# PinguinoUCAB.net
KiCad netlist of a schematic drawn in EAGLE
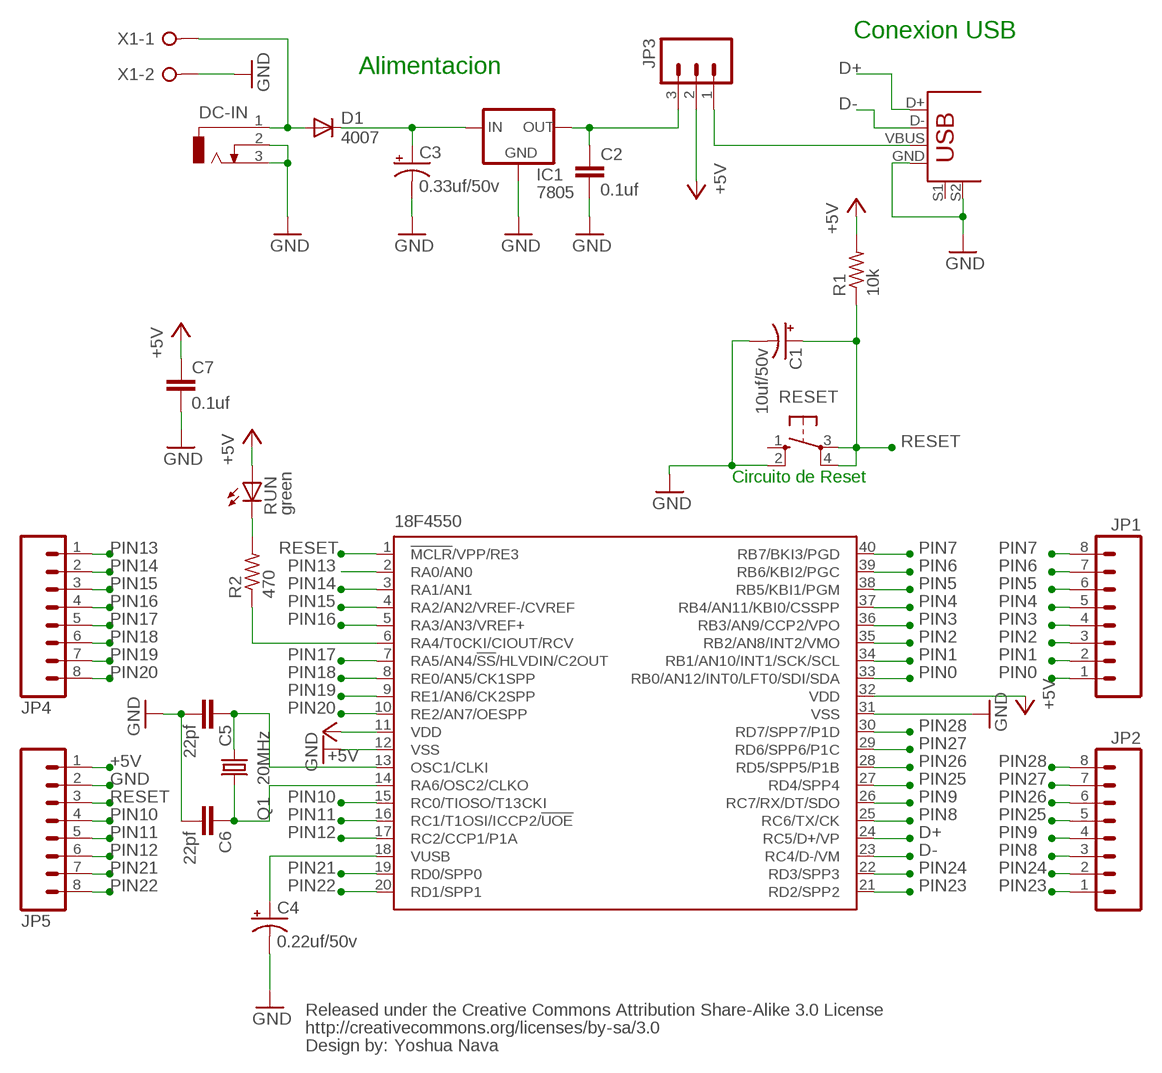
[diagram p0: schematic, sheet 1]

(export (version "E")
  (design (tool "Eeschema 10.0.6"))
  (components
    (comp (ref "18F4550")
      (value "PIC18F4550_40")
      (footprint "eagle-import:DIL40")
      (fields (field (name "MF") "MICROCHIP") (field (name "MPN") "PIC18F4550-I/P"))
      (libsource (lib "eagle-import") (part "PIC18F4_40550"))
    )
    (comp (ref "C1")
      (value "10uf/50v")
      (footprint "eagle-import:CPOL-RADIAL-10UF-25V")
      (libsource (lib "eagle-import") (part "CAP_POLPTH2"))
    )
    (comp (ref "C2")
      (value "0.1uf")
      (footprint "eagle-import:CAP-PTH-SMALL2")
      (libsource (lib "eagle-import") (part "CAPPTH2"))
    )
    (comp (ref "C3")
      (value "0.33uf/50v")
      (footprint "eagle-import:CPOL-RADIAL-10UF-25V")
      (libsource (lib "eagle-import") (part "CAP_POLPTH2"))
    )
    (comp (ref "C4")
      (value "0.22uf/50v")
      (footprint "eagle-import:CPOL-RADIAL-10UF-25V")
      (libsource (lib "eagle-import") (part "CAP_POLPTH2"))
    )
    (comp (ref "C5")
      (value "22pf")
      (footprint "eagle-import:CAP-PTH-SMALL2")
      (libsource (lib "eagle-import") (part "CAPPTH2"))
    )
    (comp (ref "C6")
      (value "22pf")
      (footprint "eagle-import:CAP-PTH-SMALL2")
      (libsource (lib "eagle-import") (part "CAPPTH2"))
    )
    (comp (ref "C7")
      (value "0.1uf")
      (footprint "eagle-import:CAP-PTH-SMALL2")
      (libsource (lib "eagle-import") (part "CAPPTH2"))
    )
    (comp (ref "CC_TEXT1")
      (value "CREATIVE_COMMONS")
      (footprint "eagle-import:CREATIVE_COMMONS")
      (libsource (lib "eagle-import") (part "CREATIVE_COMMONS"))
    )
    (comp (ref "D1")
      (value "4007")
      (footprint "eagle-import:DO35-7")
      (libsource (lib "eagle-import") (part "1N4148DO35-7"))
    )
    (comp (ref "DC-IN")
      (value "DCJ0303")
      (footprint "eagle-import:DCJ0303")
      (libsource (lib "eagle-import") (part "DCJ0303"))
    )
    (comp (ref "IC1")
      (value "7805")
      (footprint "eagle-import:78XXL")
      (libsource (lib "eagle-import") (part "78XXL"))
    )
    (comp (ref "JP1")
      (value "M08LONGPADS")
      (footprint "eagle-import:1X08_LONGPADS")
      (libsource (lib "eagle-import") (part "M08LONGPADS"))
    )
    (comp (ref "JP2")
      (value "M08LONGPADS")
      (footprint "eagle-import:1X08_LONGPADS")
      (libsource (lib "eagle-import") (part "M08LONGPADS"))
    )
    (comp (ref "JP3")
      (value "M03LONGPADS")
      (footprint "eagle-import:1X03_LONGPADS")
      (libsource (lib "eagle-import") (part "M03LONGPADS"))
    )
    (comp (ref "JP4")
      (value "M08LONGPADS")
      (footprint "eagle-import:1X08_LONGPADS")
      (libsource (lib "eagle-import") (part "M08LONGPADS"))
    )
    (comp (ref "JP5")
      (value "M08LONGPADS")
      (footprint "eagle-import:1X08_LONGPADS")
      (libsource (lib "eagle-import") (part "M08LONGPADS"))
    )
    (comp (ref "Q1")
      (value "20MHz")
      (footprint "eagle-import:HC49U-V")
      (libsource (lib "eagle-import") (part "CRYSTALHC49U-V"))
    )
    (comp (ref "R1")
      (value "10k")
      (footprint "eagle-import:0207_7")
      (libsource (lib "eagle-import") (part "R-US_0207/7"))
    )
    (comp (ref "R2")
      (value "470")
      (footprint "eagle-import:0207_7")
      (libsource (lib "eagle-import") (part "R-US_0207/7"))
    )
    (comp (ref "RESET")
      (value "10-XX")
      (footprint "eagle-import:B3F-10XX")
      (fields (field (name "MPN") "B3F-1000"))
      (libsource (lib "eagle-import") (part "10-XX"))
    )
    (comp (ref "RUN")
      (value "green")
      (footprint "eagle-import:LED3MM")
      (libsource (lib "eagle-import") (part "LED3MM"))
    )
    (comp (ref "USB")
      (value "USB+SHIELD")
      (footprint "eagle-import:USB-B-PTH")
      (libsource (lib "eagle-import") (part "USB+SHIELD"))
    )
    (comp (ref "X1")
      (value "W237-02P")
      (footprint "eagle-import:W237-132")
      (libsource (lib "eagle-import") (part "W237-02P"))
    )
  )
  (nets
    (net (code "1") (name "+5V") (class "Default")
      (node (ref "18F4550") (pin "11") (pinfunction "VDD_11") (pintype "power_in"))
      (node (ref "18F4550") (pin "32") (pinfunction "VDD_32") (pintype "power_in"))
      (node (ref "C7") (pin "1") (pinfunction "1_1") (pintype "passive"))
      (node (ref "JP3") (pin "2") (pinfunction "2_2") (pintype "passive"))
      (node (ref "JP5") (pin "1") (pinfunction "1_1") (pintype "passive"))
      (node (ref "R1") (pin "2") (pinfunction "2_2") (pintype "passive"))
      (node (ref "RUN") (pin "A") (pinfunction "A_A") (pintype "passive"))
    )
    (net (code "2") (name "/D+") (class "Default")
      (node (ref "18F4550") (pin "24") (pinfunction "RC5/D+/VP_24") (pintype "bidirectional"))
      (node (ref "USB") (pin "D+") (pinfunction "D+_D+") (pintype "bidirectional"))
    )
    (net (code "3") (name "/D-") (class "Default")
      (node (ref "18F4550") (pin "23") (pinfunction "RC4/D-/VM_23") (pintype "bidirectional"))
      (node (ref "USB") (pin "D-") (pinfunction "D-_D-") (pintype "bidirectional"))
    )
    (net (code "4") (name "/PIN0") (class "Default")
      (node (ref "18F4550") (pin "33") (pinfunction "RB0/AN12/INT0/LFT0/SDI/SDA_33") (pintype "bidirectional"))
      (node (ref "JP1") (pin "1") (pinfunction "1_1") (pintype "passive"))
    )
    (net (code "5") (name "/PIN1") (class "Default")
      (node (ref "18F4550") (pin "34") (pinfunction "RB1/AN10/INT1/SCK/SCL_34") (pintype "bidirectional"))
      (node (ref "JP1") (pin "2") (pinfunction "2_2") (pintype "passive"))
    )
    (net (code "6") (name "/PIN2") (class "Default")
      (node (ref "18F4550") (pin "35") (pinfunction "RB2/AN8/INT2/VMO_35") (pintype "bidirectional"))
      (node (ref "JP1") (pin "3") (pinfunction "3_3") (pintype "passive"))
    )
    (net (code "7") (name "/PIN3") (class "Default")
      (node (ref "18F4550") (pin "36") (pinfunction "RB3/AN9/CCP2/VPO_36") (pintype "bidirectional"))
      (node (ref "JP1") (pin "4") (pinfunction "4_4") (pintype "passive"))
    )
    (net (code "8") (name "/PIN4") (class "Default")
      (node (ref "18F4550") (pin "37") (pinfunction "RB4/AN11/KBI0/CSSPP_37") (pintype "bidirectional"))
      (node (ref "JP1") (pin "5") (pinfunction "5_5") (pintype "passive"))
    )
    (net (code "9") (name "/PIN5") (class "Default")
      (node (ref "18F4550") (pin "38") (pinfunction "RB5/KBI1/PGM_38") (pintype "bidirectional"))
      (node (ref "JP1") (pin "6") (pinfunction "6_6") (pintype "passive"))
    )
    (net (code "10") (name "/PIN6") (class "Default")
      (node (ref "18F4550") (pin "39") (pinfunction "RB6/KBI2/PGC_39") (pintype "bidirectional"))
      (node (ref "JP1") (pin "7") (pinfunction "7_7") (pintype "passive"))
    )
    (net (code "11") (name "/PIN7") (class "Default")
      (node (ref "18F4550") (pin "40") (pinfunction "RB7/BKI3/PGD_40") (pintype "bidirectional"))
      (node (ref "JP1") (pin "8") (pinfunction "8_8") (pintype "passive"))
    )
    (net (code "12") (name "/PIN8") (class "Default")
      (node (ref "18F4550") (pin "25") (pinfunction "RC6/TX/CK_25") (pintype "bidirectional"))
      (node (ref "JP2") (pin "3") (pinfunction "3_3") (pintype "passive"))
    )
    (net (code "13") (name "/PIN9") (class "Default")
      (node (ref "18F4550") (pin "26") (pinfunction "RC7/RX/DT/SDO_26") (pintype "bidirectional"))
      (node (ref "JP2") (pin "4") (pinfunction "4_4") (pintype "passive"))
    )
    (net (code "14") (name "/PIN10") (class "Default")
      (node (ref "18F4550") (pin "15") (pinfunction "RC0/TIOSO/T13CKI_15") (pintype "bidirectional"))
      (node (ref "JP5") (pin "4") (pinfunction "4_4") (pintype "passive"))
    )
    (net (code "15") (name "/PIN11") (class "Default")
      (node (ref "18F4550") (pin "16") (pinfunction "RC1/T1OSI/ICCP2/~{UOE}_16") (pintype "bidirectional"))
      (node (ref "JP5") (pin "5") (pinfunction "5_5") (pintype "passive"))
    )
    (net (code "16") (name "/PIN12") (class "Default")
      (node (ref "18F4550") (pin "17") (pinfunction "RC2/CCP1/P1A_17") (pintype "bidirectional"))
      (node (ref "JP5") (pin "6") (pinfunction "6_6") (pintype "passive"))
    )
    (net (code "17") (name "/PIN13") (class "Default")
      (node (ref "18F4550") (pin "2") (pinfunction "RA0/AN0_2") (pintype "bidirectional"))
      (node (ref "JP4") (pin "1") (pinfunction "1_1") (pintype "passive"))
    )
    (net (code "18") (name "/PIN14") (class "Default")
      (node (ref "18F4550") (pin "3") (pinfunction "RA1/AN1_3") (pintype "bidirectional"))
      (node (ref "JP4") (pin "2") (pinfunction "2_2") (pintype "passive"))
    )
    (net (code "19") (name "/PIN15") (class "Default")
      (node (ref "18F4550") (pin "4") (pinfunction "RA2/AN2/VREF-/CVREF_4") (pintype "bidirectional"))
      (node (ref "JP4") (pin "3") (pinfunction "3_3") (pintype "passive"))
    )
    (net (code "20") (name "/PIN16") (class "Default")
      (node (ref "18F4550") (pin "5") (pinfunction "RA3/AN3/VREF+_5") (pintype "bidirectional"))
      (node (ref "JP4") (pin "4") (pinfunction "4_4") (pintype "passive"))
    )
    (net (code "21") (name "/PIN17") (class "Default")
      (node (ref "18F4550") (pin "7") (pinfunction "RA5/AN4/~{SS}/HLVDIN/C2OUT_7") (pintype "bidirectional"))
      (node (ref "JP4") (pin "5") (pinfunction "5_5") (pintype "passive"))
    )
    (net (code "22") (name "/PIN18") (class "Default")
      (node (ref "18F4550") (pin "8") (pinfunction "RE0/AN5/CK1SPP_8") (pintype "bidirectional"))
      (node (ref "JP4") (pin "6") (pinfunction "6_6") (pintype "passive"))
    )
    (net (code "23") (name "/PIN19") (class "Default")
      (node (ref "18F4550") (pin "9") (pinfunction "RE1/AN6/CK2SPP_9") (pintype "bidirectional"))
      (node (ref "JP4") (pin "7") (pinfunction "7_7") (pintype "passive"))
    )
    (net (code "24") (name "/PIN20") (class "Default")
      (node (ref "18F4550") (pin "10") (pinfunction "RE2/AN7/OESPP_10") (pintype "bidirectional"))
      (node (ref "JP4") (pin "8") (pinfunction "8_8") (pintype "passive"))
    )
    (net (code "25") (name "/PIN21") (class "Default")
      (node (ref "18F4550") (pin "19") (pinfunction "RD0/SPP0_19") (pintype "bidirectional"))
      (node (ref "JP5") (pin "7") (pinfunction "7_7") (pintype "passive"))
    )
    (net (code "26") (name "/PIN22") (class "Default")
      (node (ref "18F4550") (pin "20") (pinfunction "RD1/SPP1_20") (pintype "bidirectional"))
      (node (ref "JP5") (pin "8") (pinfunction "8_8") (pintype "passive"))
    )
    (net (code "27") (name "/PIN23") (class "Default")
      (node (ref "18F4550") (pin "21") (pinfunction "RD2/SPP2_21") (pintype "bidirectional"))
      (node (ref "JP2") (pin "1") (pinfunction "1_1") (pintype "passive"))
    )
    (net (code "28") (name "/PIN24") (class "Default")
      (node (ref "18F4550") (pin "22") (pinfunction "RD3/SPP3_22") (pintype "bidirectional"))
      (node (ref "JP2") (pin "2") (pinfunction "2_2") (pintype "passive"))
    )
    (net (code "29") (name "/PIN25") (class "Default")
      (node (ref "18F4550") (pin "27") (pinfunction "RD4/SPP4_27") (pintype "bidirectional"))
      (node (ref "JP2") (pin "5") (pinfunction "5_5") (pintype "passive"))
    )
    (net (code "30") (name "/PIN26") (class "Default")
      (node (ref "18F4550") (pin "28") (pinfunction "RD5/SPP5/P1B_28") (pintype "bidirectional"))
      (node (ref "JP2") (pin "6") (pinfunction "6_6") (pintype "passive"))
    )
    (net (code "31") (name "/PIN27") (class "Default")
      (node (ref "18F4550") (pin "29") (pinfunction "RD6/SPP6/P1C_29") (pintype "bidirectional"))
      (node (ref "JP2") (pin "7") (pinfunction "7_7") (pintype "passive"))
    )
    (net (code "32") (name "/PIN28") (class "Default")
      (node (ref "18F4550") (pin "30") (pinfunction "RD7/SPP7/P1D_30") (pintype "bidirectional"))
      (node (ref "JP2") (pin "8") (pinfunction "8_8") (pintype "passive"))
    )
    (net (code "33") (name "/RESET") (class "Default")
      (node (ref "18F4550") (pin "1") (pinfunction "~{MCLR}/VPP/RE3_1") (pintype "input"))
      (node (ref "C1") (pin "1") (pinfunction "+_1") (pintype "passive"))
      (node (ref "JP5") (pin "3") (pinfunction "3_3") (pintype "passive"))
      (node (ref "R1") (pin "1") (pinfunction "1_1") (pintype "passive"))
      (node (ref "RESET") (pin "3") (pinfunction "P_3") (pintype "passive"))
      (node (ref "RESET") (pin "4") (pinfunction "P1_4") (pintype "passive"))
    )
    (net (code "34") (name "GND") (class "Default")
      (node (ref "18F4550") (pin "12") (pinfunction "VSS_12") (pintype "power_in"))
      (node (ref "18F4550") (pin "31") (pinfunction "VSS_31") (pintype "power_in"))
      (node (ref "C1") (pin "2") (pinfunction "-_2") (pintype "passive"))
      (node (ref "C2") (pin "2") (pinfunction "2_2") (pintype "passive"))
      (node (ref "C3") (pin "2") (pinfunction "-_2") (pintype "passive"))
      (node (ref "C4") (pin "2") (pinfunction "-_2") (pintype "passive"))
      (node (ref "C5") (pin "2") (pinfunction "2_2") (pintype "passive"))
      (node (ref "C6") (pin "2") (pinfunction "2_2") (pintype "passive"))
      (node (ref "C7") (pin "2") (pinfunction "2_2") (pintype "passive"))
      (node (ref "DC-IN") (pin "2") (pinfunction "2_2") (pintype "passive"))
      (node (ref "DC-IN") (pin "3") (pinfunction "3_3") (pintype "passive"))
      (node (ref "IC1") (pin "GND") (pinfunction "GND_GND") (pintype "input"))
      (node (ref "JP5") (pin "2") (pinfunction "2_2") (pintype "passive"))
      (node (ref "RESET") (pin "2") (pinfunction "S1_2") (pintype "passive"))
      (node (ref "USB") (pin "GND") (pinfunction "GND_GND") (pintype "bidirectional"))
      (node (ref "USB") (pin "S2") (pinfunction "P$2_S2") (pintype "bidirectional"))
      (node (ref "X1") (pin "2") (pinfunction "KL_2") (pintype "passive"))
    )
    (net (code "35") (name "Net-(18F4550-OSC1{slash}CLKI)") (class "Default")
      (node (ref "18F4550") (pin "13") (pinfunction "OSC1/CLKI_13") (pintype "input"))
      (node (ref "C5") (pin "1") (pinfunction "1_1") (pintype "passive"))
      (node (ref "Q1") (pin "1") (pinfunction "1_1") (pintype "passive"))
    )
    (net (code "36") (name "Net-(18F4550-RA4{slash}T0CKI{slash}CIOUT{slash}RCV)") (class "Default")
      (node (ref "18F4550") (pin "6") (pinfunction "RA4/T0CKI/CIOUT/RCV_6") (pintype "bidirectional"))
      (node (ref "R2") (pin "1") (pinfunction "1_1") (pintype "passive"))
    )
    (net (code "37") (name "Net-(18F4550-RA6{slash}OSC2{slash}CLKO)") (class "Default")
      (node (ref "18F4550") (pin "14") (pinfunction "RA6/OSC2/CLKO_14") (pintype "output"))
      (node (ref "C6") (pin "1") (pinfunction "1_1") (pintype "passive"))
      (node (ref "Q1") (pin "2") (pinfunction "2_2") (pintype "passive"))
    )
    (net (code "38") (name "Net-(18F4550-VUSB)") (class "Default")
      (node (ref "18F4550") (pin "18") (pinfunction "VUSB_18") (pintype "bidirectional"))
      (node (ref "C4") (pin "1") (pinfunction "+_1") (pintype "passive"))
    )
    (net (code "39") (name "Net-(C2-Pad1)") (class "Default")
      (node (ref "C2") (pin "1") (pinfunction "1_1") (pintype "passive"))
      (node (ref "IC1") (pin "OUT") (pinfunction "OUT_OUT") (pintype "passive"))
      (node (ref "JP3") (pin "3") (pinfunction "3_3") (pintype "passive"))
    )
    (net (code "40") (name "Net-(C3-+)") (class "Default")
      (node (ref "C3") (pin "1") (pinfunction "+_1") (pintype "passive"))
      (node (ref "D1") (pin "C") (pinfunction "C_C") (pintype "passive"))
      (node (ref "IC1") (pin "IN") (pinfunction "IN_IN") (pintype "input"))
    )
    (net (code "41") (name "Net-(JP3-Pad1)") (class "Default")
      (node (ref "JP3") (pin "1") (pinfunction "1_1") (pintype "passive"))
      (node (ref "USB") (pin "VBUS") (pinfunction "VBUS_VBUS") (pintype "bidirectional"))
    )
    (net (code "42") (name "Net-(RUN-C)") (class "Default")
      (node (ref "R2") (pin "2") (pinfunction "2_2") (pintype "passive"))
      (node (ref "RUN") (pin "K") (pinfunction "C_K") (pintype "passive"))
    )
    (net (code "43") (name "Net-(X1A-KL)") (class "Default")
      (node (ref "D1") (pin "A") (pinfunction "A_A") (pintype "passive"))
      (node (ref "DC-IN") (pin "1") (pinfunction "1_1") (pintype "passive"))
      (node (ref "X1") (pin "1") (pinfunction "KL_1") (pintype "passive"))
    )
    (net (code "44") (name "unconnected-(RESET-S-Pad1)") (class "Default")
      (node (ref "RESET") (pin "1") (pinfunction "S_1") (pintype "passive"))
    )
    (net (code "45") (name "unconnected-(USB-P$1-PadS1)") (class "Default")
      (node (ref "USB") (pin "S1") (pinfunction "P$1_S1") (pintype "bidirectional"))
    )
  )
)
